# Expansion_Connector.net
KiCad netlist of a schematic drawn in Altium Designer
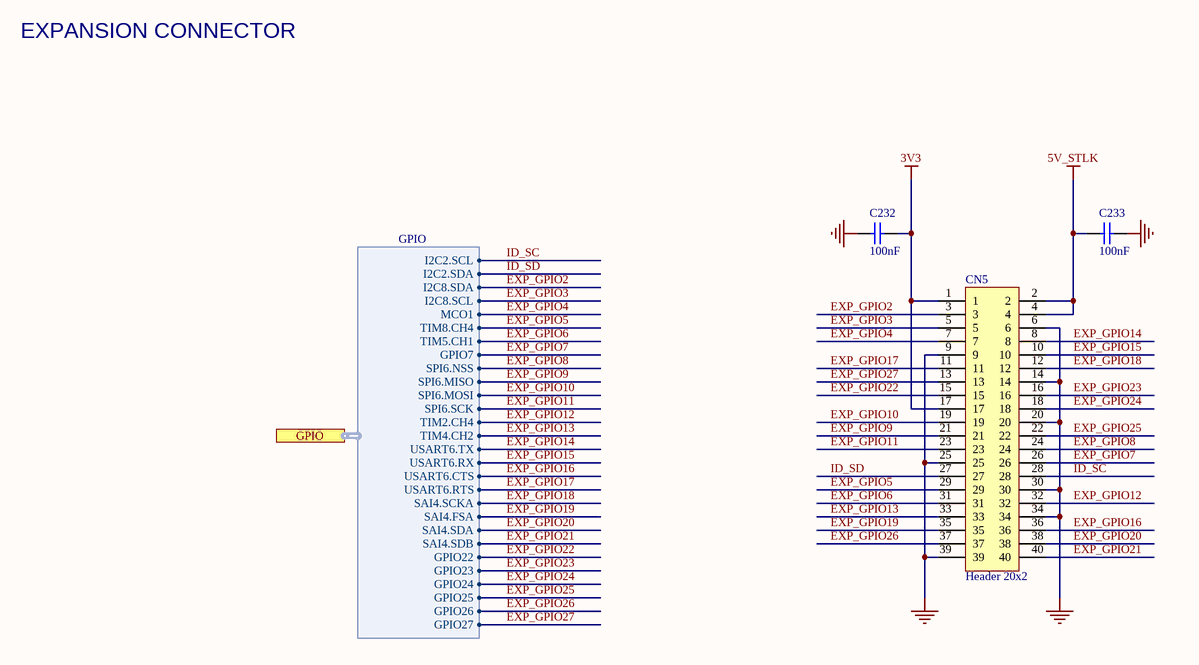
[diagram p0: Expansion_Connector.SchDoc]

(export (version "E")
  (design (tool "Eeschema 10.0.6"))
  (components
    (comp (ref "C232")
      (value "100nF")
      (footprint "C0402")
      (description "Capacitor, MLCC, 100nF, 16V, X7R, +/-10%, 0402, T=0.5mm")
      (fields (field (name "INTERNAL_PART_NUMBER") "MCD-00006") (field (name "MANUFACTURER") "YAGEO"))
      (libsource (lib "MCD_PARTS_database") (part "Capacitor"))
    )
    (comp (ref "C233")
      (value "100nF")
      (footprint "C0402")
      (description "Capacitor, MLCC, 100nF, 16V, X7R, +/-10%, 0402, T=0.5mm")
      (fields (field (name "INTERNAL_PART_NUMBER") "MCD-00006") (field (name "MANUFACTURER") "YAGEO"))
      (libsource (lib "MCD_PARTS_database") (part "Capacitor"))
    )
    (comp (ref "CN5")
      (value "Header 20x2")
      (footprint "CON_SAMTEC_TSW-120-07-G-D")
      (description "Header, 20x2, 2.54mm, VR, TH, T=5.84mm/2.54mm")
      (fields
        (field (name "INTERNAL_PART_NUMBER") "MCD-00302")
        (field (name "MANUFACTURER_PART_NUMBER") "TSW-120-07-G-D")
      )
      (libsource (lib "MCD_PARTS_database") (part "Header 20x2"))
    )
  )
  (nets
    (net (code "2") (name "/EXP_GPIO2") (class "Default")
      (node (ref "CN5") (pin "3") (pinfunction "3_3") (pintype "passive"))
    )
    (net (code "3") (name "/EXP_GPIO3") (class "Default")
      (node (ref "CN5") (pin "5") (pinfunction "5_5") (pintype "passive"))
    )
    (net (code "4") (name "/EXP_GPIO4") (class "Default")
      (node (ref "CN5") (pin "7") (pinfunction "7_7") (pintype "passive"))
    )
    (net (code "5") (name "/EXP_GPIO5") (class "Default")
      (node (ref "CN5") (pin "29") (pinfunction "29_29") (pintype "passive"))
    )
    (net (code "6") (name "/EXP_GPIO6") (class "Default")
      (node (ref "CN5") (pin "31") (pinfunction "31_31") (pintype "passive"))
    )
    (net (code "7") (name "/EXP_GPIO7") (class "Default")
      (node (ref "CN5") (pin "26") (pinfunction "26_26") (pintype "passive"))
    )
    (net (code "8") (name "/EXP_GPIO8") (class "Default")
      (node (ref "CN5") (pin "24") (pinfunction "24_24") (pintype "passive"))
    )
    (net (code "9") (name "/EXP_GPIO9") (class "Default")
      (node (ref "CN5") (pin "21") (pinfunction "21_21") (pintype "passive"))
    )
    (net (code "10") (name "/EXP_GPIO10") (class "Default")
      (node (ref "CN5") (pin "19") (pinfunction "19_19") (pintype "passive"))
    )
    (net (code "11") (name "/EXP_GPIO11") (class "Default")
      (node (ref "CN5") (pin "23") (pinfunction "23_23") (pintype "passive"))
    )
    (net (code "12") (name "/EXP_GPIO12") (class "Default")
      (node (ref "CN5") (pin "32") (pinfunction "32_32") (pintype "passive"))
    )
    (net (code "13") (name "/EXP_GPIO13") (class "Default")
      (node (ref "CN5") (pin "33") (pinfunction "33_33") (pintype "passive"))
    )
    (net (code "14") (name "/EXP_GPIO14") (class "Default")
      (node (ref "CN5") (pin "8") (pinfunction "8_8") (pintype "passive"))
    )
    (net (code "15") (name "/EXP_GPIO15") (class "Default")
      (node (ref "CN5") (pin "10") (pinfunction "10_10") (pintype "passive"))
    )
    (net (code "16") (name "/EXP_GPIO16") (class "Default")
      (node (ref "CN5") (pin "36") (pinfunction "36_36") (pintype "passive"))
    )
    (net (code "17") (name "/EXP_GPIO17") (class "Default")
      (node (ref "CN5") (pin "11") (pinfunction "11_11") (pintype "passive"))
    )
    (net (code "18") (name "/EXP_GPIO18") (class "Default")
      (node (ref "CN5") (pin "12") (pinfunction "12_12") (pintype "passive"))
    )
    (net (code "19") (name "/EXP_GPIO19") (class "Default")
      (node (ref "CN5") (pin "35") (pinfunction "35_35") (pintype "passive"))
    )
    (net (code "20") (name "/EXP_GPIO20") (class "Default")
      (node (ref "CN5") (pin "38") (pinfunction "38_38") (pintype "passive"))
    )
    (net (code "21") (name "/EXP_GPIO21") (class "Default")
      (node (ref "CN5") (pin "40") (pinfunction "40_40") (pintype "passive"))
    )
    (net (code "22") (name "/EXP_GPIO22") (class "Default")
      (node (ref "CN5") (pin "15") (pinfunction "15_15") (pintype "passive"))
    )
    (net (code "23") (name "/EXP_GPIO23") (class "Default")
      (node (ref "CN5") (pin "16") (pinfunction "16_16") (pintype "passive"))
    )
    (net (code "24") (name "/EXP_GPIO24") (class "Default")
      (node (ref "CN5") (pin "18") (pinfunction "18_18") (pintype "passive"))
    )
    (net (code "25") (name "/EXP_GPIO25") (class "Default")
      (node (ref "CN5") (pin "22") (pinfunction "22_22") (pintype "passive"))
    )
    (net (code "26") (name "/EXP_GPIO26") (class "Default")
      (node (ref "CN5") (pin "37") (pinfunction "37_37") (pintype "passive"))
    )
    (net (code "27") (name "/EXP_GPIO27") (class "Default")
      (node (ref "CN5") (pin "13") (pinfunction "13_13") (pintype "passive"))
    )
    (net (code "28") (name "/ID_SC") (class "Default")
      (node (ref "CN5") (pin "28") (pinfunction "28_28") (pintype "passive"))
    )
    (net (code "29") (name "/ID_SD") (class "Default")
      (node (ref "CN5") (pin "27") (pinfunction "27_27") (pintype "passive"))
    )
    (net (code "31") (name "3V3") (class "Default")
      (node (ref "C232") (pin "1") (pinfunction "1_1") (pintype "passive"))
      (node (ref "CN5") (pin "1") (pinfunction "1_1") (pintype "passive"))
      (node (ref "CN5") (pin "17") (pinfunction "17_17") (pintype "passive"))
    )
    (net (code "32") (name "5V_STLK") (class "Default")
      (node (ref "C233") (pin "2") (pinfunction "2_2") (pintype "passive"))
      (node (ref "CN5") (pin "2") (pinfunction "2_2") (pintype "passive"))
      (node (ref "CN5") (pin "4") (pinfunction "4_4") (pintype "passive"))
    )
    (net (code "33") (name "GND") (class "Default")
      (node (ref "C232") (pin "2") (pinfunction "2_2") (pintype "passive"))
      (node (ref "C233") (pin "1") (pinfunction "1_1") (pintype "passive"))
      (node (ref "CN5") (pin "14") (pinfunction "14_14") (pintype "passive"))
      (node (ref "CN5") (pin "20") (pinfunction "20_20") (pintype "passive"))
      (node (ref "CN5") (pin "25") (pinfunction "25_25") (pintype "passive"))
      (node (ref "CN5") (pin "30") (pinfunction "30_30") (pintype "passive"))
      (node (ref "CN5") (pin "34") (pinfunction "34_34") (pintype "passive"))
      (node (ref "CN5") (pin "39") (pinfunction "39_39") (pintype "passive"))
      (node (ref "CN5") (pin "6") (pinfunction "6_6") (pintype "passive"))
      (node (ref "CN5") (pin "9") (pinfunction "9_9") (pintype "passive"))
    )
  )
)
